# pomodoro.net
KiCad netlist of a schematic drawn in EAGLE
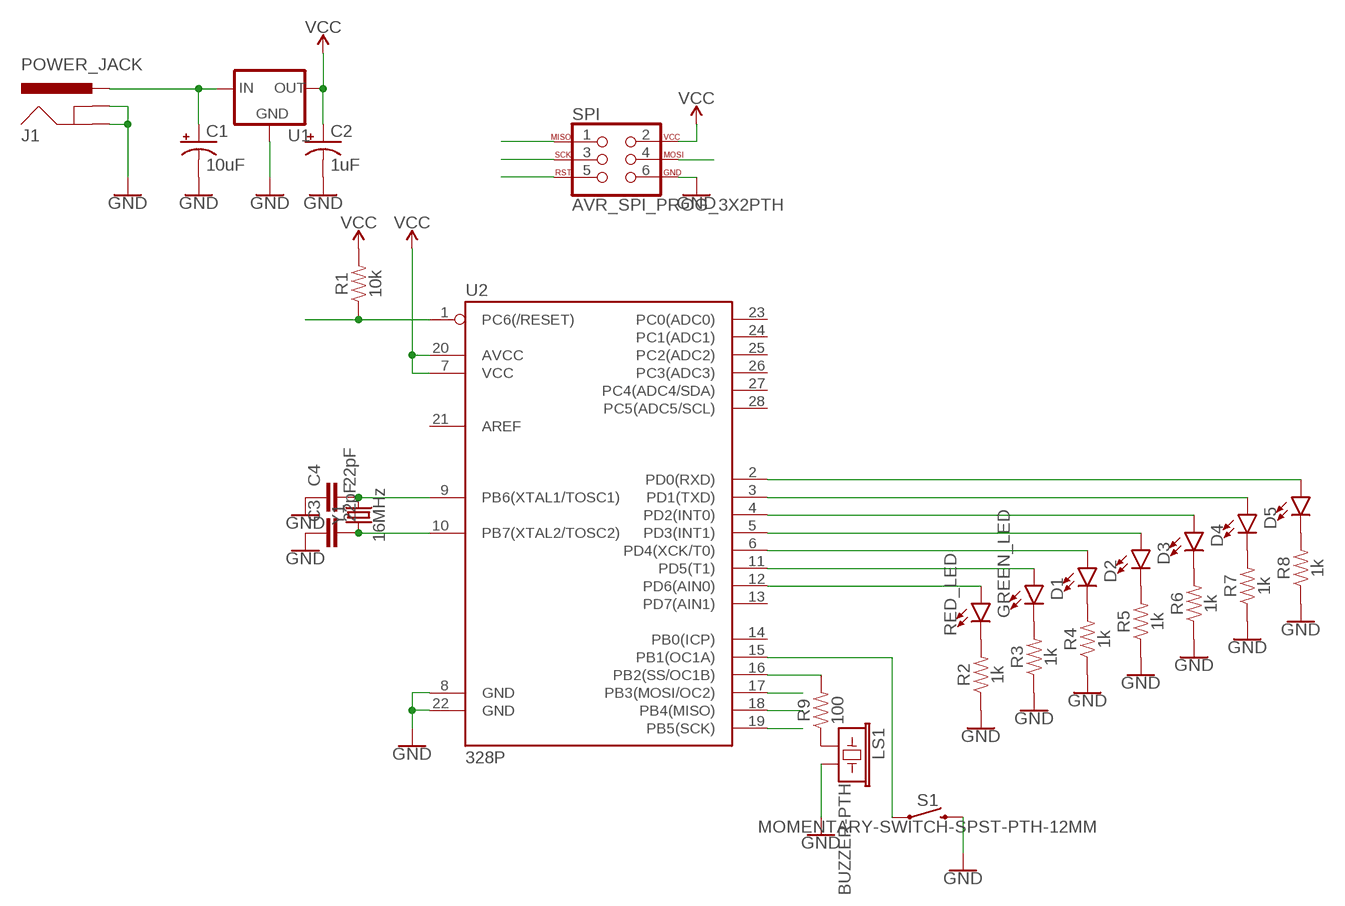
[diagram p0: schematic, sheet 1]

(export (version "E")
  (design (tool "Eeschema 10.0.6"))
  (components
    (comp (ref "C1")
      (value "10uF")
      (footprint "eagle-import:CPOL-RADIAL-2.5MM-5MM")
      (libsource (lib "eagle-import") (part "10UF-POLAR-RADIAL-2.5MM-25V-20%"))
    )
    (comp (ref "C2")
      (value "1uF")
      (footprint "eagle-import:CPOL-RADIAL-2.5MM-5MM")
      (libsource (lib "eagle-import") (part "10UF-POLAR-RADIAL-2.5MM-25V-20%"))
    )
    (comp (ref "C3")
      (value "22pF")
      (footprint "eagle-import:CAP-PTH-2.54")
      (libsource (lib "eagle-import") (part "22PF-PTH-2.54MM-200V-5%"))
    )
    (comp (ref "C4")
      (value "22pF")
      (footprint "eagle-import:CAP-PTH-2.54")
      (libsource (lib "eagle-import") (part "22PF-PTH-2.54MM-200V-5%"))
    )
    (comp (ref "D1")
      (value "LED5MM")
      (footprint "eagle-import:LED_5MM")
      (libsource (lib "eagle-import") (part "LED5MM"))
    )
    (comp (ref "D2")
      (value "LED5MM")
      (footprint "eagle-import:LED_5MM")
      (libsource (lib "eagle-import") (part "LED5MM"))
    )
    (comp (ref "D3")
      (value "LED5MM")
      (footprint "eagle-import:LED_5MM")
      (libsource (lib "eagle-import") (part "LED5MM"))
    )
    (comp (ref "D4")
      (value "LED5MM")
      (footprint "eagle-import:LED_5MM")
      (libsource (lib "eagle-import") (part "LED5MM"))
    )
    (comp (ref "D5")
      (value "LED5MM")
      (footprint "eagle-import:LED_5MM")
      (libsource (lib "eagle-import") (part "LED5MM"))
    )
    (comp (ref "GREEN_LED")
      (value "LED5MM")
      (footprint "eagle-import:LED_5MM")
      (libsource (lib "eagle-import") (part "LED5MM"))
    )
    (comp (ref "J1")
      (value "POWER_JACK")
      (footprint "eagle-import:POWER_JACK_PTH")
      (libsource (lib "eagle-import") (part "POWER_JACK"))
    )
    (comp (ref "LS1")
      (value "BUZZER-PTH")
      (footprint "eagle-import:BUZZER-12MM")
      (libsource (lib "eagle-import") (part "BUZZER-PTH"))
    )
    (comp (ref "R1")
      (value "10k")
      (footprint "eagle-import:AXIAL-0.3")
      (libsource (lib "eagle-import") (part "1KOHM-HORIZ-1/4W-1%"))
    )
    (comp (ref "R2")
      (value "1k")
      (footprint "eagle-import:AXIAL-0.3")
      (libsource (lib "eagle-import") (part "1KOHM-HORIZ-1/4W-1%"))
    )
    (comp (ref "R3")
      (value "1k")
      (footprint "eagle-import:AXIAL-0.3")
      (libsource (lib "eagle-import") (part "1KOHM-HORIZ-1/4W-1%"))
    )
    (comp (ref "R4")
      (value "1k")
      (footprint "eagle-import:AXIAL-0.3")
      (libsource (lib "eagle-import") (part "1KOHM-HORIZ-1/4W-1%"))
    )
    (comp (ref "R5")
      (value "1k")
      (footprint "eagle-import:AXIAL-0.3")
      (libsource (lib "eagle-import") (part "1KOHM-HORIZ-1/4W-1%"))
    )
    (comp (ref "R6")
      (value "1k")
      (footprint "eagle-import:AXIAL-0.3")
      (libsource (lib "eagle-import") (part "1KOHM-HORIZ-1/4W-1%"))
    )
    (comp (ref "R7")
      (value "1k")
      (footprint "eagle-import:AXIAL-0.3")
      (libsource (lib "eagle-import") (part "1KOHM-HORIZ-1/4W-1%"))
    )
    (comp (ref "R8")
      (value "1k")
      (footprint "eagle-import:AXIAL-0.3")
      (libsource (lib "eagle-import") (part "1KOHM-HORIZ-1/4W-1%"))
    )
    (comp (ref "R9")
      (value "100")
      (footprint "eagle-import:AXIAL-0.3")
      (libsource (lib "eagle-import") (part "1KOHM-HORIZ-1/4W-1%"))
    )
    (comp (ref "RED_LED")
      (value "LED5MM")
      (footprint "eagle-import:LED_5MM")
      (libsource (lib "eagle-import") (part "LED5MM"))
    )
    (comp (ref "S1")
      (value "MOMENTARY-SWITCH-SPST-PTH-12MM")
      (footprint "eagle-import:TACTILE_SWITCH_PTH_12MM")
      (libsource (lib "eagle-import") (part "MOMENTARY-SWITCH-SPST-PTH-12MM"))
    )
    (comp (ref "SPI")
      (value "AVR_SPI_PROG_3X2PTH")
      (footprint "eagle-import:2X3")
      (libsource (lib "eagle-import") (part "AVR_SPI_PROG_3X2PTH"))
    )
    (comp (ref "U1")
      (value "V_REG_78XX-TO-220")
      (footprint "eagle-import:TO-220-ALT")
      (libsource (lib "eagle-import") (part "V_REG_78XX-TO-220"))
    )
    (comp (ref "U2")
      (value "328P")
      (footprint "eagle-import:DIP28")
      (libsource (lib "eagle-import") (part "ATMEGA328P_PDIP"))
    )
    (comp (ref "Y1")
      (value "16MHz")
      (footprint "eagle-import:HC49US")
      (libsource (lib "eagle-import") (part "CRYSTAL-16MHZPTH-HC49US"))
    )
  )
  (nets
    (net (code "1") (name "/MISO") (class "Default")
      (node (ref "SPI") (pin "1") (pinfunction "1_1") (pintype "passive"))
      (node (ref "U2") (pin "18") (pinfunction "PB4(MISO)_18") (pintype "bidirectional"))
    )
    (net (code "2") (name "/MOSI") (class "Default")
      (node (ref "SPI") (pin "4") (pinfunction "4_4") (pintype "passive"))
      (node (ref "U2") (pin "17") (pinfunction "PB3(MOSI/OC2)_17") (pintype "bidirectional"))
    )
    (net (code "3") (name "/RST") (class "Default")
      (node (ref "R1") (pin "P$1") (pinfunction "1_P$1") (pintype "passive"))
      (node (ref "SPI") (pin "5") (pinfunction "5_5") (pintype "passive"))
      (node (ref "U2") (pin "1") (pinfunction "PC6(/RESET)_1") (pintype "bidirectional"))
    )
    (net (code "4") (name "/SCK") (class "Default")
      (node (ref "SPI") (pin "3") (pinfunction "3_3") (pintype "passive"))
      (node (ref "U2") (pin "19") (pinfunction "PB5(SCK)_19") (pintype "bidirectional"))
    )
    (net (code "5") (name "GND") (class "Default")
      (node (ref "C1") (pin "2") (pinfunction "-_2") (pintype "passive"))
      (node (ref "C2") (pin "2") (pinfunction "-_2") (pintype "passive"))
      (node (ref "C3") (pin "1") (pinfunction "1_1") (pintype "passive"))
      (node (ref "C4") (pin "1") (pinfunction "1_1") (pintype "passive"))
      (node (ref "J1") (pin "GND") (pinfunction "GND_GND") (pintype "bidirectional"))
      (node (ref "J1") (pin "GNDBREAK") (pinfunction "GNDBREAK_GNDBREAK") (pintype "bidirectional"))
      (node (ref "LS1") (pin "-") (pinfunction "2_-") (pintype "passive"))
      (node (ref "R2") (pin "P$1") (pinfunction "1_P$1") (pintype "passive"))
      (node (ref "R3") (pin "P$1") (pinfunction "1_P$1") (pintype "passive"))
      (node (ref "R4") (pin "P$1") (pinfunction "1_P$1") (pintype "passive"))
      (node (ref "R5") (pin "P$1") (pinfunction "1_P$1") (pintype "passive"))
      (node (ref "R6") (pin "P$1") (pinfunction "1_P$1") (pintype "passive"))
      (node (ref "R7") (pin "P$1") (pinfunction "1_P$1") (pintype "passive"))
      (node (ref "R8") (pin "P$1") (pinfunction "1_P$1") (pintype "passive"))
      (node (ref "S1") (pin "3") (pinfunction "2_3") (pintype "passive"))
      (node (ref "SPI") (pin "6") (pinfunction "6_6") (pintype "passive"))
      (node (ref "U1") (pin "GND") (pinfunction "GND_GND") (pintype "input"))
      (node (ref "U2") (pin "22") (pinfunction "GND_22") (pintype "bidirectional"))
      (node (ref "U2") (pin "8") (pinfunction "GND_8") (pintype "bidirectional"))
    )
    (net (code "6") (name "Net-(C1-+)") (class "Default")
      (node (ref "C1") (pin "1") (pinfunction "+_1") (pintype "passive"))
      (node (ref "J1") (pin "PWR") (pinfunction "PWR_PWR") (pintype "bidirectional"))
      (node (ref "U1") (pin "IN") (pinfunction "IN_IN") (pintype "input"))
    )
    (net (code "7") (name "Net-(D1-C)") (class "Default")
      (node (ref "D1") (pin "K") (pinfunction "C_K") (pintype "passive"))
      (node (ref "R4") (pin "P$2") (pinfunction "2_P$2") (pintype "passive"))
    )
    (net (code "8") (name "Net-(D2-C)") (class "Default")
      (node (ref "D2") (pin "K") (pinfunction "C_K") (pintype "passive"))
      (node (ref "R5") (pin "P$2") (pinfunction "2_P$2") (pintype "passive"))
    )
    (net (code "9") (name "Net-(D3-C)") (class "Default")
      (node (ref "D3") (pin "K") (pinfunction "C_K") (pintype "passive"))
      (node (ref "R6") (pin "P$2") (pinfunction "2_P$2") (pintype "passive"))
    )
    (net (code "10") (name "Net-(D4-C)") (class "Default")
      (node (ref "D4") (pin "K") (pinfunction "C_K") (pintype "passive"))
      (node (ref "R7") (pin "P$2") (pinfunction "2_P$2") (pintype "passive"))
    )
    (net (code "11") (name "Net-(D5-C)") (class "Default")
      (node (ref "D5") (pin "K") (pinfunction "C_K") (pintype "passive"))
      (node (ref "R8") (pin "P$2") (pinfunction "2_P$2") (pintype "passive"))
    )
    (net (code "12") (name "Net-(GREEN_LED-C)") (class "Default")
      (node (ref "GREEN_LED") (pin "K") (pinfunction "C_K") (pintype "passive"))
      (node (ref "R3") (pin "P$2") (pinfunction "2_P$2") (pintype "passive"))
    )
    (net (code "13") (name "Net-(LS1-1)") (class "Default")
      (node (ref "LS1") (pin "+") (pinfunction "1_+") (pintype "passive"))
      (node (ref "R9") (pin "P$1") (pinfunction "1_P$1") (pintype "passive"))
    )
    (net (code "14") (name "Net-(R2-2)") (class "Default")
      (node (ref "R2") (pin "P$2") (pinfunction "2_P$2") (pintype "passive"))
      (node (ref "RED_LED") (pin "K") (pinfunction "C_K") (pintype "passive"))
    )
    (net (code "15") (name "Net-(R9-2)") (class "Default")
      (node (ref "R9") (pin "P$2") (pinfunction "2_P$2") (pintype "passive"))
      (node (ref "U2") (pin "16") (pinfunction "PB2(SS/OC1B)_16") (pintype "bidirectional"))
    )
    (net (code "16") (name "Net-(U2-PB1(OC1A))") (class "Default")
      (node (ref "S1") (pin "1") (pinfunction "1_1") (pintype "passive"))
      (node (ref "U2") (pin "15") (pinfunction "PB1(OC1A)_15") (pintype "bidirectional"))
    )
    (net (code "17") (name "Net-(U2-PB6(XTAL1{slash}TOSC1))") (class "Default")
      (node (ref "C4") (pin "2") (pinfunction "2_2") (pintype "passive"))
      (node (ref "U2") (pin "9") (pinfunction "PB6(XTAL1/TOSC1)_9") (pintype "bidirectional"))
      (node (ref "Y1") (pin "2") (pinfunction "2_2") (pintype "passive"))
    )
    (net (code "18") (name "Net-(U2-PB7(XTAL2{slash}TOSC2))") (class "Default")
      (node (ref "C3") (pin "2") (pinfunction "2_2") (pintype "passive"))
      (node (ref "U2") (pin "10") (pinfunction "PB7(XTAL2/TOSC2)_10") (pintype "bidirectional"))
      (node (ref "Y1") (pin "1") (pinfunction "1_1") (pintype "passive"))
    )
    (net (code "19") (name "Net-(U2-PD0(RXD))") (class "Default")
      (node (ref "D5") (pin "A") (pinfunction "A_A") (pintype "passive"))
      (node (ref "U2") (pin "2") (pinfunction "PD0(RXD)_2") (pintype "bidirectional"))
    )
    (net (code "20") (name "Net-(U2-PD1(TXD))") (class "Default")
      (node (ref "D4") (pin "A") (pinfunction "A_A") (pintype "passive"))
      (node (ref "U2") (pin "3") (pinfunction "PD1(TXD)_3") (pintype "bidirectional"))
    )
    (net (code "21") (name "Net-(U2-PD2(INT0))") (class "Default")
      (node (ref "D3") (pin "A") (pinfunction "A_A") (pintype "passive"))
      (node (ref "U2") (pin "4") (pinfunction "PD2(INT0)_4") (pintype "bidirectional"))
    )
    (net (code "22") (name "Net-(U2-PD3(INT1))") (class "Default")
      (node (ref "D2") (pin "A") (pinfunction "A_A") (pintype "passive"))
      (node (ref "U2") (pin "5") (pinfunction "PD3(INT1)_5") (pintype "bidirectional"))
    )
    (net (code "23") (name "Net-(U2-PD4(XCK{slash}T0))") (class "Default")
      (node (ref "D1") (pin "A") (pinfunction "A_A") (pintype "passive"))
      (node (ref "U2") (pin "6") (pinfunction "PD4(XCK/T0)_6") (pintype "bidirectional"))
    )
    (net (code "24") (name "Net-(U2-PD5(T1))") (class "Default")
      (node (ref "GREEN_LED") (pin "A") (pinfunction "A_A") (pintype "passive"))
      (node (ref "U2") (pin "11") (pinfunction "PD5(T1)_11") (pintype "bidirectional"))
    )
    (net (code "25") (name "Net-(U2-PD6(AIN0))") (class "Default")
      (node (ref "RED_LED") (pin "A") (pinfunction "A_A") (pintype "passive"))
      (node (ref "U2") (pin "12") (pinfunction "PD6(AIN0)_12") (pintype "bidirectional"))
    )
    (net (code "26") (name "VCC") (class "Default")
      (node (ref "C2") (pin "1") (pinfunction "+_1") (pintype "passive"))
      (node (ref "R1") (pin "P$2") (pinfunction "2_P$2") (pintype "passive"))
      (node (ref "SPI") (pin "2") (pinfunction "2_2") (pintype "passive"))
      (node (ref "U1") (pin "OUT") (pinfunction "OUT_OUT") (pintype "passive"))
      (node (ref "U2") (pin "20") (pinfunction "AVCC_20") (pintype "bidirectional"))
      (node (ref "U2") (pin "7") (pinfunction "VCC_7") (pintype "bidirectional"))
    )
    (net (code "27") (name "unconnected-(U2-AREF-Pad21)") (class "Default")
      (node (ref "U2") (pin "21") (pinfunction "AREF_21") (pintype "bidirectional"))
    )
    (net (code "28") (name "unconnected-(U2-PB0(ICP)-Pad14)") (class "Default")
      (node (ref "U2") (pin "14") (pinfunction "PB0(ICP)_14") (pintype "bidirectional"))
    )
    (net (code "29") (name "unconnected-(U2-PC0(ADC0)-Pad23)") (class "Default")
      (node (ref "U2") (pin "23") (pinfunction "PC0(ADC0)_23") (pintype "bidirectional"))
    )
    (net (code "30") (name "unconnected-(U2-PC1(ADC1)-Pad24)") (class "Default")
      (node (ref "U2") (pin "24") (pinfunction "PC1(ADC1)_24") (pintype "bidirectional"))
    )
    (net (code "31") (name "unconnected-(U2-PC2(ADC2)-Pad25)") (class "Default")
      (node (ref "U2") (pin "25") (pinfunction "PC2(ADC2)_25") (pintype "bidirectional"))
    )
    (net (code "32") (name "unconnected-(U2-PC3(ADC3)-Pad26)") (class "Default")
      (node (ref "U2") (pin "26") (pinfunction "PC3(ADC3)_26") (pintype "bidirectional"))
    )
    (net (code "33") (name "unconnected-(U2-PC4(ADC4{slash}SDA)-Pad27)") (class "Default")
      (node (ref "U2") (pin "27") (pinfunction "PC4(ADC4/SDA)_27") (pintype "bidirectional"))
    )
    (net (code "34") (name "unconnected-(U2-PC5(ADC5{slash}SCL)-Pad28)") (class "Default")
      (node (ref "U2") (pin "28") (pinfunction "PC5(ADC5/SCL)_28") (pintype "bidirectional"))
    )
    (net (code "35") (name "unconnected-(U2-PD7(AIN1)-Pad13)") (class "Default")
      (node (ref "U2") (pin "13") (pinfunction "PD7(AIN1)_13") (pintype "bidirectional"))
    )
  )
)
